# USB.net
KiCad netlist of a schematic drawn in Altium Designer
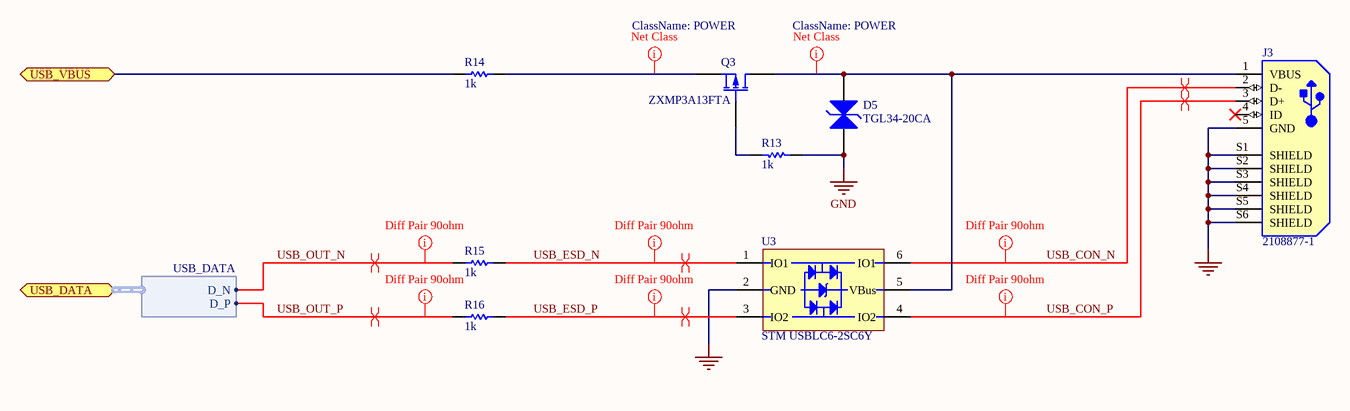
[diagram p0: USB.SchDoc]

(export (version "E")
  (design (tool "Eeschema 10.0.6"))
  (components
    (comp (ref "D5")
      (value "TGL34-20CA")
      (footprint "DIO_MELF_IPC_MD")
      (description "Transil")
      (libsource (lib "agh_racing_2018") (part "TGL34-20CA"))
    )
    (comp (ref "J3")
      (value "2108877-1")
      (footprint "MicroUSB_2108877-1")
      (description "TE Connectivity")
      (libsource (lib "agh_racing_2018") (part "MicroUSB 2108877-1"))
    )
    (comp (ref "Q3")
      (value "ZXMP3A13FTA")
      (footprint "SOT23_IPC_MD")
      (description "P-mosfet")
      (libsource (lib "agh_racing_2018") (part "ZXMP3A13FTA"))
    )
    (comp (ref "R13")
      (value "1k")
      (footprint "agh_racing_2018:RES_0603_IPC_MD")
      (description "Resistor")
      (fields (field (name "Comment") "Res"))
      (libsource (lib "agh_racing_2018") (part "Res"))
    )
    (comp (ref "R14")
      (value "1k")
      (footprint "agh_racing_2018:RES_0603_IPC_MD")
      (description "Resistor")
      (fields (field (name "Comment") "Res"))
      (libsource (lib "agh_racing_2018") (part "Res"))
    )
    (comp (ref "R15")
      (value "1k")
      (footprint "agh_racing_2018:RES_0603_IPC_MD")
      (description "Resistor")
      (fields (field (name "Comment") "Res"))
      (libsource (lib "agh_racing_2018") (part "Res"))
    )
    (comp (ref "R16")
      (value "1k")
      (footprint "agh_racing_2018:RES_0603_IPC_MD")
      (description "Resistor")
      (fields (field (name "Comment") "Res"))
      (libsource (lib "agh_racing_2018") (part "Res"))
    )
    (comp (ref "U3")
      (value "STM USBLC6-2SC6Y")
      (footprint "SOT23-6L_IPC_MD")
      (description "Automotive very low capacitance ESD protection (USB)")
      (libsource (lib "agh_racing_2018") (part "USBLC6-2SC6Y"))
    )
  )
  (nets
    (net (code "2") (name "/USB_CON_N") (class "Default")
      (node (ref "J3") (pin "2") (pinfunction "D-_2") (pintype "bidirectional"))
      (node (ref "U3") (pin "6") (pinfunction "IO1_6") (pintype "passive"))
    )
    (net (code "3") (name "/USB_CON_P") (class "Default")
      (node (ref "J3") (pin "3") (pinfunction "D+_3") (pintype "bidirectional"))
      (node (ref "U3") (pin "4") (pinfunction "IO2_4") (pintype "passive"))
    )
    (net (code "4") (name "/USB_ESD_N") (class "Default")
      (node (ref "R15") (pin "2") (pinfunction "2_2") (pintype "passive"))
      (node (ref "U3") (pin "1") (pinfunction "IO1_1") (pintype "passive"))
    )
    (net (code "5") (name "/USB_ESD_P") (class "Default")
      (node (ref "R16") (pin "2") (pinfunction "2_2") (pintype "passive"))
      (node (ref "U3") (pin "3") (pinfunction "IO2_3") (pintype "power_in"))
    )
    (net (code "6") (name "/USB_OUT_N") (class "Default")
      (node (ref "R15") (pin "1") (pinfunction "1_1") (pintype "passive"))
    )
    (net (code "7") (name "/USB_OUT_P") (class "Default")
      (node (ref "R16") (pin "1") (pinfunction "1_1") (pintype "passive"))
    )
    (net (code "8") (name "/USB_VBUS") (class "Default")
      (node (ref "R14") (pin "1") (pinfunction "1_1") (pintype "passive"))
    )
    (net (code "10") (name "GND") (class "Default")
      (node (ref "D5") (pin "1") (pinfunction "IN1_1") (pintype "passive"))
      (node (ref "J3") (pin "5") (pinfunction "GND_5") (pintype "power_in"))
      (node (ref "J3") (pin "S1") (pinfunction "SHIELD_S1") (pintype "passive"))
      (node (ref "J3") (pin "S2") (pinfunction "SHIELD_S2") (pintype "passive"))
      (node (ref "J3") (pin "S3") (pinfunction "SHIELD_S3") (pintype "passive"))
      (node (ref "J3") (pin "S4") (pinfunction "SHIELD_S4") (pintype "passive"))
      (node (ref "J3") (pin "S5") (pinfunction "SHIELD_S5") (pintype "passive"))
      (node (ref "J3") (pin "S6") (pinfunction "SHIELD_S6") (pintype "passive"))
      (node (ref "R13") (pin "2") (pinfunction "2_2") (pintype "passive"))
      (node (ref "U3") (pin "2") (pinfunction "GND_2") (pintype "passive"))
    )
    (net (code "11") (name "Net-(D5-IN2)") (class "Default")
      (node (ref "D5") (pin "2") (pinfunction "IN2_2") (pintype "passive"))
      (node (ref "J3") (pin "1") (pinfunction "VBUS_1") (pintype "power_in"))
      (node (ref "Q3") (pin "3") (pinfunction "D_3") (pintype "passive"))
      (node (ref "U3") (pin "5") (pinfunction "VBus_5") (pintype "passive"))
    )
    (net (code "12") (name "Net-(Q3-G)") (class "Default")
      (node (ref "Q3") (pin "1") (pinfunction "G_1") (pintype "passive"))
      (node (ref "R13") (pin "1") (pinfunction "1_1") (pintype "passive"))
    )
    (net (code "13") (name "Net-(Q3-S)") (class "Default")
      (node (ref "Q3") (pin "2") (pinfunction "S_2") (pintype "passive"))
      (node (ref "R14") (pin "2") (pinfunction "2_2") (pintype "passive"))
    )
    (net (code "14") (name "unconnected-(J3-ID-Pad4)") (class "Default")
      (node (ref "J3") (pin "4") (pinfunction "ID_4") (pintype "bidirectional+no_connect"))
    )
  )
)
